# PaxInstrument-T400-at90usb.net
KiCad netlist of a schematic drawn in EAGLE
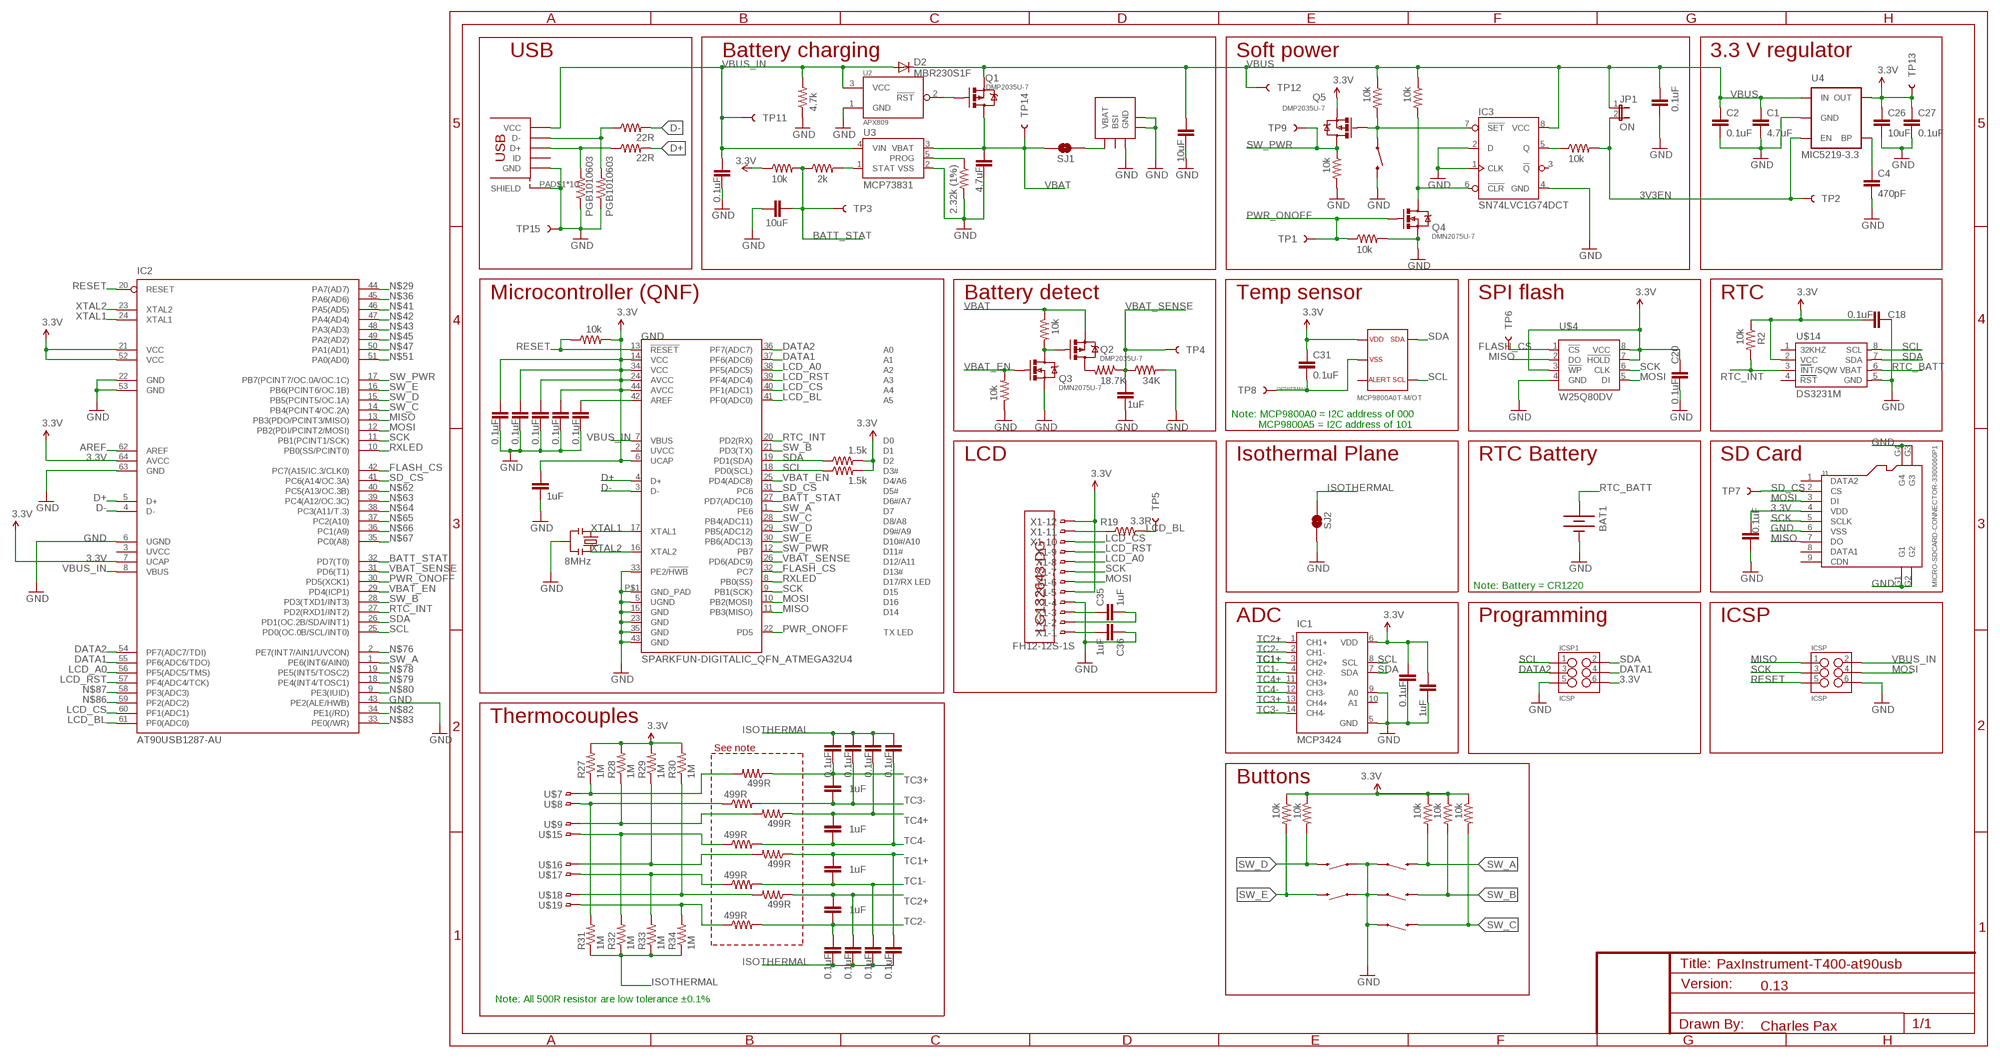
[diagram p0: schematic, sheet 1]

(export (version "E")
  (design (tool "Eeschema 10.0.6"))
  (components
    (comp (ref "BAT1")
      (value "BATTERY12MM")
      (footprint "eagle-import:BATTCON_12MM")
      (fields (field (name "MF") "Keystone Electronics") (field (name "MPN") "3000TR"))
      (libsource (lib "eagle-import") (part "BATTERY12MM"))
    )
    (comp (ref "C1")
      (value "4.7uF")
      (footprint "eagle-import:SPARKFUN-CAPACITORS_0603-CAP")
      (libsource (lib "eagle-import") (part "SPARKFUN-CAPACITORS_CAP0603-CAP"))
    )
    (comp (ref "C2")
      (value "0.1uF")
      (footprint "eagle-import:SPARKFUN-CAPACITORS_0603-CAP")
      (libsource (lib "eagle-import") (part "SPARKFUN-CAPACITORS_CAP0603-CAP"))
    )
    (comp (ref "C3")
      (value "0.1uF")
      (footprint "eagle-import:SPARKFUN-CAPACITORS_0603-CAP")
      (libsource (lib "eagle-import") (part "SPARKFUN-CAPACITORS_CAP0603-CAP"))
    )
    (comp (ref "C4")
      (value "470pF")
      (footprint "eagle-import:SPARKFUN-CAPACITORS_0603-CAP")
      (libsource (lib "eagle-import") (part "SPARKFUN-CAPACITORS_CAP0603-CAP"))
    )
    (comp (ref "C5")
      (value "0.1uF")
      (footprint "eagle-import:SPARKFUN-CAPACITORS_0603-CAP")
      (libsource (lib "eagle-import") (part "SPARKFUN-CAPACITORS_CAP0603-CAP"))
    )
    (comp (ref "C6")
      (value "0.1uF")
      (footprint "eagle-import:SPARKFUN-CAPACITORS_0603-CAP")
      (libsource (lib "eagle-import") (part "SPARKFUN-CAPACITORS_CAP0603-CAP"))
    )
    (comp (ref "C7")
      (value "1uF")
      (footprint "eagle-import:SPARKFUN-CAPACITORS_0603-CAP")
      (libsource (lib "eagle-import") (part "SPARKFUN-CAPACITORS_CAP0603-CAP"))
    )
    (comp (ref "C8")
      (value "1uF")
      (footprint "eagle-import:SPARKFUN-CAPACITORS_0603-CAP")
      (libsource (lib "eagle-import") (part "SPARKFUN-CAPACITORS_CAP0603-CAP"))
    )
    (comp (ref "C9")
      (value "4.7uF")
      (footprint "eagle-import:SPARKFUN-CAPACITORS_0603-CAP")
      (libsource (lib "eagle-import") (part "SPARKFUN-CAPACITORS_CAP0603-CAP"))
    )
    (comp (ref "C10")
      (value "1uF")
      (footprint "eagle-import:SPARKFUN-CAPACITORS_0603-CAP")
      (libsource (lib "eagle-import") (part "SPARKFUN-CAPACITORS_CAP0603-CAP"))
    )
    (comp (ref "C11")
      (value "1uF")
      (footprint "eagle-import:SPARKFUN-CAPACITORS_0603-CAP")
      (libsource (lib "eagle-import") (part "SPARKFUN-CAPACITORS_CAP0603-CAP"))
    )
    (comp (ref "C12")
      (value "10uF")
      (footprint "eagle-import:SPARKFUN-CAPACITORS_0603-CAP")
      (libsource (lib "eagle-import") (part "SPARKFUN-CAPACITORS_CAP0603-CAP"))
    )
    (comp (ref "C13")
      (value "0.1uF")
      (footprint "eagle-import:SPARKFUN-CAPACITORS_0603-CAP")
      (libsource (lib "eagle-import") (part "SPARKFUN-CAPACITORS_CAP0603-CAP"))
    )
    (comp (ref "C14")
      (value "0.1uF")
      (footprint "eagle-import:SPARKFUN-CAPACITORS_0603-CAP")
      (libsource (lib "eagle-import") (part "SPARKFUN-CAPACITORS_CAP0603-CAP"))
    )
    (comp (ref "C15")
      (value "0.1uF")
      (footprint "eagle-import:SPARKFUN-CAPACITORS_0603-CAP")
      (libsource (lib "eagle-import") (part "SPARKFUN-CAPACITORS_CAP0603-CAP"))
    )
    (comp (ref "C16")
      (value "0.1uF")
      (footprint "eagle-import:SPARKFUN-CAPACITORS_0603-CAP")
      (libsource (lib "eagle-import") (part "SPARKFUN-CAPACITORS_CAP0603-CAP"))
    )
    (comp (ref "C17")
      (value "0.1uF")
      (footprint "eagle-import:SPARKFUN-CAPACITORS_0603-CAP")
      (libsource (lib "eagle-import") (part "SPARKFUN-CAPACITORS_CAP0603-CAP"))
    )
    (comp (ref "C18")
      (value "0.1uF")
      (footprint "eagle-import:SPARKFUN-CAPACITORS_0603-CAP")
      (libsource (lib "eagle-import") (part "SPARKFUN-CAPACITORS_CAP0603-CAP"))
    )
    (comp (ref "C19")
      (value "1uF")
      (footprint "eagle-import:SPARKFUN-CAPACITORS_0603-CAP")
      (libsource (lib "eagle-import") (part "SPARKFUN-CAPACITORS_CAP0603-CAP"))
    )
    (comp (ref "C20")
      (value "0.1uF")
      (footprint "eagle-import:SPARKFUN-CAPACITORS_0603-CAP")
      (libsource (lib "eagle-import") (part "SPARKFUN-CAPACITORS_CAP0603-CAP"))
    )
    (comp (ref "C21")
      (value "0.1uF")
      (footprint "eagle-import:SPARKFUN-CAPACITORS_0603-CAP")
      (libsource (lib "eagle-import") (part "SPARKFUN-CAPACITORS_CAP0603-CAP"))
    )
    (comp (ref "C22")
      (value "10uF")
      (footprint "eagle-import:SPARKFUN-CAPACITORS_0603-CAP")
      (libsource (lib "eagle-import") (part "SPARKFUN-CAPACITORS_CAP0603-CAP"))
    )
    (comp (ref "C23")
      (value "1uF")
      (footprint "eagle-import:SPARKFUN-CAPACITORS_0603-CAP")
      (libsource (lib "eagle-import") (part "SPARKFUN-CAPACITORS_CAP0603-CAP"))
    )
    (comp (ref "C24")
      (value "0.1uF")
      (footprint "eagle-import:SPARKFUN-CAPACITORS_0603-CAP")
      (libsource (lib "eagle-import") (part "SPARKFUN-CAPACITORS_CAP0603-CAP"))
    )
    (comp (ref "C25")
      (value "0.1uF")
      (footprint "eagle-import:SPARKFUN-CAPACITORS_0603-CAP")
      (libsource (lib "eagle-import") (part "SPARKFUN-CAPACITORS_CAP0603-CAP"))
    )
    (comp (ref "C26")
      (value "10uF")
      (footprint "eagle-import:SPARKFUN-CAPACITORS_0603-CAP")
      (libsource (lib "eagle-import") (part "SPARKFUN-CAPACITORS_CAP0603-CAP"))
    )
    (comp (ref "C27")
      (value "0.1uF")
      (footprint "eagle-import:SPARKFUN-CAPACITORS_0603-CAP")
      (libsource (lib "eagle-import") (part "SPARKFUN-CAPACITORS_CAP0603-CAP"))
    )
    (comp (ref "C28")
      (value "0.1uF")
      (footprint "eagle-import:SPARKFUN-CAPACITORS_0603-CAP")
      (libsource (lib "eagle-import") (part "SPARKFUN-CAPACITORS_CAP0603-CAP"))
    )
    (comp (ref "C29")
      (value "0.1uF")
      (footprint "eagle-import:SPARKFUN-CAPACITORS_0603-CAP")
      (libsource (lib "eagle-import") (part "SPARKFUN-CAPACITORS_CAP0603-CAP"))
    )
    (comp (ref "C30")
      (value "1uF")
      (footprint "eagle-import:SPARKFUN-CAPACITORS_0603-CAP")
      (libsource (lib "eagle-import") (part "SPARKFUN-CAPACITORS_CAP0603-CAP"))
    )
    (comp (ref "C31")
      (value "0.1uF")
      (footprint "eagle-import:SPARKFUN-CAPACITORS_0603-CAP")
      (libsource (lib "eagle-import") (part "SPARKFUN-CAPACITORS_CAP0603-CAP"))
    )
    (comp (ref "C32")
      (value "0.1uF")
      (footprint "eagle-import:SPARKFUN-CAPACITORS_0603-CAP")
      (libsource (lib "eagle-import") (part "SPARKFUN-CAPACITORS_CAP0603-CAP"))
    )
    (comp (ref "C33")
      (value "0.1uF")
      (footprint "eagle-import:SPARKFUN-CAPACITORS_0603-CAP")
      (libsource (lib "eagle-import") (part "SPARKFUN-CAPACITORS_CAP0603-CAP"))
    )
    (comp (ref "C34")
      (value "0.1uF")
      (footprint "eagle-import:SPARKFUN-CAPACITORS_0603-CAP")
      (libsource (lib "eagle-import") (part "SPARKFUN-CAPACITORS_CAP0603-CAP"))
    )
    (comp (ref "C35")
      (value "1uF")
      (footprint "eagle-import:SPARKFUN-CAPACITORS_0603-CAP")
      (libsource (lib "eagle-import") (part "SPARKFUN-CAPACITORS_CAP0603-CAP"))
    )
    (comp (ref "C36")
      (value "1uF")
      (footprint "eagle-import:SPARKFUN-CAPACITORS_0603-CAP")
      (libsource (lib "eagle-import") (part "SPARKFUN-CAPACITORS_CAP0603-CAP"))
    )
    (comp (ref "C37")
      (value "0.1uF")
      (footprint "eagle-import:SPARKFUN-CAPACITORS_0603-CAP")
      (libsource (lib "eagle-import") (part "SPARKFUN-CAPACITORS_CAP0603-CAP"))
    )
    (comp (ref "D2")
      (value "MBR230S1F")
      (footprint "eagle-import:SOD123")
      (fields (field (name "MF") "DIODES INC") (field (name "MPN") "MBR230S1F-7"))
      (libsource (lib "eagle-import") (part "SPARKFUN-DISCRETESEMI_DIODESOD123SOD123"))
    )
    (comp (ref "GND")
      (value "SPARKFUN-DIGITALIC_QFN_ATMEGA32U4")
      (footprint "eagle-import:SPARKFUN-DIGITALIC_SPARKFUN-DIGITALIC_QFN-44")
      (fields (field (name "MF") "Atmel") (field (name "MPN") "ATMEGA32U4-MU"))
      (libsource (lib "eagle-import") (part "SPARKFUN-DIGITALIC_QFN_ATMEGA32U4"))
    )
    (comp (ref "IC1")
      (value "MCP3424")
      (footprint "eagle-import:SO14")
      (fields (field (name "MF") "Microchip Technology") (field (name "MPN") "MCP3424-E/SL"))
      (libsource (lib "eagle-import") (part "MCP3424"))
    )
    (comp (ref "IC2")
      (value "AT90USB1287-AU")
      (footprint "eagle-import:TQFP64")
      (libsource (lib "eagle-import") (part "AT90USB1287-AU"))
    )
    (comp (ref "IC3")
      (value "SN74LVC1G74DCT")
      (footprint "eagle-import:SSOP8")
      (fields (field (name "MF") "Texas Instruments") (field (name "MPN") "SN74LVC1G74DCTR "))
      (libsource (lib "eagle-import") (part "SN74LVC1G74DCT"))
    )
    (comp (ref "ICSP")
      (value "ICSP")
      (footprint "eagle-import:SPARKFUN-CONNECTORS_2X3_SMT_POSTS_PAXINSTRUMENT")
      (fields (field (name "MF") "FCI") (field (name "MPN") "95278-101A06LF"))
      (libsource (lib "eagle-import") (part "SPARKFUN-CONNECTORS_M03X2PAX"))
    )
    (comp (ref "ICSP1")
      (value "ICSP")
      (footprint "eagle-import:SPARKFUN-CONNECTORS_2X3_SMT_POSTS_PAXINSTRUMENT")
      (fields (field (name "MF") "FCI") (field (name "MPN") "95278-101A06LF"))
      (libsource (lib "eagle-import") (part "SPARKFUN-CONNECTORS_M03X2PAX"))
    )
    (comp (ref "J1")
      (value "MICRO-SDCARD-CONNECTOR-3300060P1")
      (footprint "eagle-import:9P-SMD-W-RING")
      (fields (field (name "MF") "SUNTECH") (field (name "MPN") "ST-TF-003A"))
      (libsource (lib "eagle-import") (part "MICRO-SDCARD-CONNECTOR-3300060P1"))
    )
    (comp (ref "JP1")
      (value "ON")
      (footprint "eagle-import:SJ_2S-NO")
      (libsource (lib "eagle-import") (part "JUMPER-2SMD-NO"))
    )
    (comp (ref "Q1")
      (value "DMP2035U-7")
      (footprint "eagle-import:SOT23")
      (fields (field (name "MF") "DIODES INC"))
      (libsource (lib "eagle-import") (part "MOSFET-PCHANNELSMT"))
    )
    (comp (ref "Q2")
      (value "DMP2035U-7")
      (footprint "eagle-import:SOT23")
      (fields (field (name "MF") "DIODES INC"))
      (libsource (lib "eagle-import") (part "MOSFET-PCHANNELSMT"))
    )
    (comp (ref "Q3")
      (value "DMN2075U-7")
      (footprint "eagle-import:SOT23")
      (fields (field (name "MF") "DIODES INC") (field (name "MPN") "DMN2075U-7 "))
      (libsource (lib "eagle-import") (part "MOSFET-NCHANNELSMT"))
    )
    (comp (ref "Q4")
      (value "DMN2075U-7")
      (footprint "eagle-import:SOT23")
      (fields (field (name "MF") "DIODES INC") (field (name "MPN") "DMN2075U-7 "))
      (libsource (lib "eagle-import") (part "MOSFET-NCHANNELSMT"))
    )
    (comp (ref "Q5")
      (value "DMP2035U-7")
      (footprint "eagle-import:SOT23")
      (fields (field (name "MF") "DIODES INC"))
      (libsource (lib "eagle-import") (part "MOSFET-PCHANNELSMT"))
    )
    (comp (ref "R1")
      (value "10k")
      (footprint "eagle-import:SPARKFUN-RESISTORS_0603-RES")
      (libsource (lib "eagle-import") (part "SPARKFUN-RESISTORS_RESISTOR0603-RES"))
    )
    (comp (ref "R2")
      (value "10k")
      (footprint "eagle-import:SPARKFUN-RESISTORS_0603-RES")
      (libsource (lib "eagle-import") (part "SPARKFUN-RESISTORS_RESISTOR0603-RES"))
    )
    (comp (ref "R3")
      (value "2.32k (1%)")
      (footprint "eagle-import:SPARKFUN-RESISTORS_0603-RES")
      (libsource (lib "eagle-import") (part "SPARKFUN-RESISTORS_RESISTOR0603-RES"))
    )
    (comp (ref "R4")
      (value "10k")
      (footprint "eagle-import:SPARKFUN-RESISTORS_0603-RES")
      (libsource (lib "eagle-import") (part "SPARKFUN-RESISTORS_RESISTOR0603-RES"))
    )
    (comp (ref "R5")
      (value "10k")
      (footprint "eagle-import:SPARKFUN-RESISTORS_0603-RES")
      (libsource (lib "eagle-import") (part "SPARKFUN-RESISTORS_RESISTOR0603-RES"))
    )
    (comp (ref "R6")
      (value "10k")
      (footprint "eagle-import:SPARKFUN-RESISTORS_0603-RES")
      (libsource (lib "eagle-import") (part "SPARKFUN-RESISTORS_RESISTOR0603-RES"))
    )
    (comp (ref "R7")
      (value "10k")
      (footprint "eagle-import:SPARKFUN-RESISTORS_0603-RES")
      (libsource (lib "eagle-import") (part "SPARKFUN-RESISTORS_RESISTOR0603-RES"))
    )
    (comp (ref "R8")
      (value "10k")
      (footprint "eagle-import:SPARKFUN-RESISTORS_0603-RES")
      (libsource (lib "eagle-import") (part "SPARKFUN-RESISTORS_RESISTOR0603-RES"))
    )
    (comp (ref "R9")
      (value "22R")
      (footprint "eagle-import:SPARKFUN-RESISTORS_0603-RES")
      (libsource (lib "eagle-import") (part "SPARKFUN-RESISTORS_RESISTOR0603-RES"))
    )
    (comp (ref "R10")
      (value "22R")
      (footprint "eagle-import:SPARKFUN-RESISTORS_0603-RES")
      (libsource (lib "eagle-import") (part "SPARKFUN-RESISTORS_RESISTOR0603-RES"))
    )
    (comp (ref "R11")
      (value "10k")
      (footprint "eagle-import:SPARKFUN-RESISTORS_0603-RES")
      (libsource (lib "eagle-import") (part "SPARKFUN-RESISTORS_RESISTOR0603-RES"))
    )
    (comp (ref "R12")
      (value "10k")
      (footprint "eagle-import:SPARKFUN-RESISTORS_0603-RES")
      (libsource (lib "eagle-import") (part "SPARKFUN-RESISTORS_RESISTOR0603-RES"))
    )
    (comp (ref "R13")
      (value "1.5k")
      (footprint "eagle-import:SPARKFUN-RESISTORS_0603-RES")
      (libsource (lib "eagle-import") (part "SPARKFUN-RESISTORS_RESISTOR0603-RES"))
    )
    (comp (ref "R14")
      (value "1.5k")
      (footprint "eagle-import:SPARKFUN-RESISTORS_0603-RES")
      (libsource (lib "eagle-import") (part "SPARKFUN-RESISTORS_RESISTOR0603-RES"))
    )
    (comp (ref "R15")
      (value "10k")
      (footprint "eagle-import:SPARKFUN-RESISTORS_0603-RES")
      (libsource (lib "eagle-import") (part "SPARKFUN-RESISTORS_RESISTOR0603-RES"))
    )
    (comp (ref "R16")
      (value "10k")
      (footprint "eagle-import:SPARKFUN-RESISTORS_0603-RES")
      (libsource (lib "eagle-import") (part "SPARKFUN-RESISTORS_RESISTOR0603-RES"))
    )
    (comp (ref "R17")
      (value "2k")
      (footprint "eagle-import:SPARKFUN-RESISTORS_0603-RES")
      (libsource (lib "eagle-import") (part "SPARKFUN-RESISTORS_RESISTOR0603-RES"))
    )
    (comp (ref "R18")
      (value "10k")
      (footprint "eagle-import:SPARKFUN-RESISTORS_0603-RES")
      (libsource (lib "eagle-import") (part "SPARKFUN-RESISTORS_RESISTOR0603-RES"))
    )
    (comp (ref "R19")
      (value "3.3R")
      (footprint "eagle-import:SPARKFUN-RESISTORS_0603-RES")
      (libsource (lib "eagle-import") (part "SPARKFUN-RESISTORS_RESISTOR0603-RES"))
    )
    (comp (ref "R20")
      (value "18.7K")
      (footprint "eagle-import:SPARKFUN-RESISTORS_0603-RES")
      (libsource (lib "eagle-import") (part "SPARKFUN-RESISTORS_RESISTOR0603-RES"))
    )
    (comp (ref "R21")
      (value "10k")
      (footprint "eagle-import:SPARKFUN-RESISTORS_0603-RES")
      (libsource (lib "eagle-import") (part "SPARKFUN-RESISTORS_RESISTOR0603-RES"))
    )
    (comp (ref "R22")
      (value "10k")
      (footprint "eagle-import:SPARKFUN-RESISTORS_0603-RES")
      (libsource (lib "eagle-import") (part "SPARKFUN-RESISTORS_RESISTOR0603-RES"))
    )
    (comp (ref "R23")
      (value "10k")
      (footprint "eagle-import:SPARKFUN-RESISTORS_0603-RES")
      (libsource (lib "eagle-import") (part "SPARKFUN-RESISTORS_RESISTOR0603-RES"))
    )
    (comp (ref "R24")
      (value "34K")
      (footprint "eagle-import:SPARKFUN-RESISTORS_0603-RES")
      (libsource (lib "eagle-import") (part "SPARKFUN-RESISTORS_RESISTOR0603-RES"))
    )
    (comp (ref "R25")
      (value "4.7k")
      (footprint "eagle-import:SPARKFUN-RESISTORS_0603-RES")
      (libsource (lib "eagle-import") (part "SPARKFUN-RESISTORS_RESISTOR0603-RES"))
    )
    (comp (ref "R27")
      (value "1M")
      (footprint "eagle-import:SPARKFUN-RESISTORS_0603-RES")
      (libsource (lib "eagle-import") (part "SPARKFUN-RESISTORS_RESISTOR0603-RES"))
    )
    (comp (ref "R28")
      (value "1M")
      (footprint "eagle-import:SPARKFUN-RESISTORS_0603-RES")
      (libsource (lib "eagle-import") (part "SPARKFUN-RESISTORS_RESISTOR0603-RES"))
    )
    (comp (ref "R29")
      (value "1M")
      (footprint "eagle-import:SPARKFUN-RESISTORS_0603-RES")
      (libsource (lib "eagle-import") (part "SPARKFUN-RESISTORS_RESISTOR0603-RES"))
    )
    (comp (ref "R30")
      (value "1M")
      (footprint "eagle-import:SPARKFUN-RESISTORS_0603-RES")
      (libsource (lib "eagle-import") (part "SPARKFUN-RESISTORS_RESISTOR0603-RES"))
    )
    (comp (ref "R31")
      (value "1M")
      (footprint "eagle-import:SPARKFUN-RESISTORS_0603-RES")
      (libsource (lib "eagle-import") (part "SPARKFUN-RESISTORS_RESISTOR0603-RES"))
    )
    (comp (ref "R32")
      (value "1M")
      (footprint "eagle-import:SPARKFUN-RESISTORS_0603-RES")
      (libsource (lib "eagle-import") (part "SPARKFUN-RESISTORS_RESISTOR0603-RES"))
    )
    (comp (ref "R33")
      (value "1M")
      (footprint "eagle-import:SPARKFUN-RESISTORS_0603-RES")
      (libsource (lib "eagle-import") (part "SPARKFUN-RESISTORS_RESISTOR0603-RES"))
    )
    (comp (ref "R34")
      (value "1M")
      (footprint "eagle-import:SPARKFUN-RESISTORS_0603-RES")
      (libsource (lib "eagle-import") (part "SPARKFUN-RESISTORS_RESISTOR0603-RES"))
    )
    (comp (ref "R35")
      (value "499R")
      (footprint "eagle-import:SPARKFUN-RESISTORS_0603-RES")
      (fields (field (name "MF") "Vishay") (field (name "MPN") "TNPW0603499RBEEA"))
      (libsource (lib "eagle-import") (part "SPARKFUN-RESISTORS_RESISTOR0603-RES"))
    )
    (comp (ref "R36")
      (value "499R")
      (footprint "eagle-import:SPARKFUN-RESISTORS_0603-RES")
      (fields (field (name "MF") "Vishay") (field (name "MPN") "TNPW0603499RBEEA"))
      (libsource (lib "eagle-import") (part "SPARKFUN-RESISTORS_RESISTOR0603-RES"))
    )
    (comp (ref "R37")
      (value "499R")
      (footprint "eagle-import:SPARKFUN-RESISTORS_0603-RES")
      (fields (field (name "MF") "Vishay") (field (name "MPN") "TNPW0603499RBEEA"))
      (libsource (lib "eagle-import") (part "SPARKFUN-RESISTORS_RESISTOR0603-RES"))
    )
    (comp (ref "R38")
      (value "499R")
      (footprint "eagle-import:SPARKFUN-RESISTORS_0603-RES")
      (fields (field (name "MF") "Vishay") (field (name "MPN") "TNPW0603499RBEEA"))
      (libsource (lib "eagle-import") (part "SPARKFUN-RESISTORS_RESISTOR0603-RES"))
    )
    (comp (ref "R39")
      (value "499R")
      (footprint "eagle-import:SPARKFUN-RESISTORS_0603-RES")
      (fields (field (name "MF") "Vishay") (field (name "MPN") "TNPW0603499RBEEA"))
      (libsource (lib "eagle-import") (part "SPARKFUN-RESISTORS_RESISTOR0603-RES"))
    )
    (comp (ref "R40")
      (value "499R")
      (footprint "eagle-import:SPARKFUN-RESISTORS_0603-RES")
      (fields (field (name "MF") "Vishay") (field (name "MPN") "TNPW0603499RBEEA"))
      (libsource (lib "eagle-import") (part "SPARKFUN-RESISTORS_RESISTOR0603-RES"))
    )
    (comp (ref "R41")
      (value "499R")
      (footprint "eagle-import:SPARKFUN-RESISTORS_0603-RES")
      (fields (field (name "MF") "Vishay") (field (name "MPN") "TNPW0603499RBEEA"))
      (libsource (lib "eagle-import") (part "SPARKFUN-RESISTORS_RESISTOR0603-RES"))
    )
    (comp (ref "R42")
      (value "499R")
      (footprint "eagle-import:SPARKFUN-RESISTORS_0603-RES")
      (fields (field (name "MF") "Vishay") (field (name "MPN") "TNPW0603499RBEEA"))
      (libsource (lib "eagle-import") (part "SPARKFUN-RESISTORS_RESISTOR0603-RES"))
    )
    (comp (ref "S1")
      (value "SWITCH-MOMENTARY-2SMD")
      (footprint "eagle-import:TACTILE_SWITCH_SMD")
      (fields (field (name "MF") "C&K Components") (field (name "MPN") "RS-187R05A2-DS MT RT"))
      (libsource (lib "eagle-import") (part "SWITCH-MOMENTARY-2SMD"))
    )
    (comp (ref "S2")
      (value "SWITCH-MOMENTARY-2SMD")
      (footprint "eagle-import:TACTILE_SWITCH_SMD")
      (fields (field (name "MF") "C&K Components") (field (name "MPN") "RS-187R05A2-DS MT RT"))
      (libsource (lib "eagle-import") (part "SWITCH-MOMENTARY-2SMD"))
    )
    (comp (ref "S3")
      (value "SWITCH-MOMENTARY-2SMD")
      (footprint "eagle-import:TACTILE_SWITCH_SMD")
      (fields (field (name "MF") "C&K Components") (field (name "MPN") "RS-187R05A2-DS MT RT"))
      (libsource (lib "eagle-import") (part "SWITCH-MOMENTARY-2SMD"))
    )
    (comp (ref "S4")
      (value "SWITCH-MOMENTARY-2SMD")
      (footprint "eagle-import:TACTILE_SWITCH_SMD")
      (fields (field (name "MF") "C&K Components") (field (name "MPN") "RS-187R05A2-DS MT RT"))
      (libsource (lib "eagle-import") (part "SWITCH-MOMENTARY-2SMD"))
    )
    (comp (ref "S5")
      (value "SWITCH-MOMENTARY-2SMD")
      (footprint "eagle-import:TACTILE_SWITCH_SMD")
      (fields (field (name "MF") "C&K Components") (field (name "MPN") "RS-187R05A2-DS MT RT"))
      (libsource (lib "eagle-import") (part "SWITCH-MOMENTARY-2SMD"))
    )
    (comp (ref "S6")
      (value "SWITCH-MOMENTARY-2SMD")
      (footprint "eagle-import:TACTILE_SWITCH_SMD")
      (fields (field (name "MF") "C&K Components") (field (name "MPN") "RS-187R05A2-DS MT RT"))
      (libsource (lib "eagle-import") (part "SWITCH-MOMENTARY-2SMD"))
    )
    (comp (ref "SJ1")
      (value "JUMPER-PAD-2-NC_BY_TRACE")
      (footprint "eagle-import:PAD-JUMPER-2-NC_BY_TRACE_YES_SILK")
      (libsource (lib "eagle-import") (part "JUMPER-PAD-2-NC_BY_TRACE"))
    )
    (comp (ref "SJ2")
      (value "JUMPER-PAD-2-NC_BY_TRACE")
      (footprint "eagle-import:PAD-JUMPER-2-NC_BY_TRACE_YES_SILK")
      (libsource (lib "eagle-import") (part "JUMPER-PAD-2-NC_BY_TRACE"))
    )
    (comp (ref "TP1")
      (value "PWR_ONOFF")
      (footprint "eagle-import:TP_15TH")
      (libsource (lib "eagle-import") (part "TEST-POINTTP_15TH_THRU"))
    )
    (comp (ref "TP2")
      (value "3V3_EN")
      (footprint "eagle-import:TP_15TH")
      (libsource (lib "eagle-import") (part "TEST-POINTTP_15TH_THRU"))
    )
    (comp (ref "TP3")
      (value "BATT_STAT")
      (footprint "eagle-import:TP_15TH")
      (libsource (lib "eagle-import") (part "TEST-POINTTP_15TH_THRU"))
    )
    (comp (ref "TP4")
      (value "VBAT_SENSE")
      (footprint "eagle-import:TP_15TH")
      (libsource (lib "eagle-import") (part "TEST-POINTTP_15TH_THRU"))
    )
    (comp (ref "TP5")
      (value "LCD_BL")
      (footprint "eagle-import:TP_15TH")
      (libsource (lib "eagle-import") (part "TEST-POINTTP_15TH_THRU"))
    )
    (comp (ref "TP6")
      (value "FLASH_CS")
      (footprint "eagle-import:TP_15TH")
      (libsource (lib "eagle-import") (part "TEST-POINTTP_15TH_THRU"))
    )
    (comp (ref "TP7")
      (value "SD_CS")
      (footprint "eagle-import:TP_15TH")
      (libsource (lib "eagle-import") (part "TEST-POINTTP_15TH_THRU"))
    )
    (comp (ref "TP8")
      (value "ISOTHERMAL")
      (footprint "eagle-import:TP_15TH")
      (libsource (lib "eagle-import") (part "TEST-POINTTP_15TH_THRU"))
    )
    (comp (ref "TP9")
      (value "SW_PWR")
      (footprint "eagle-import:TP_15TH")
      (libsource (lib "eagle-import") (part "TEST-POINTTP_15TH_THRU"))
    )
    (comp (ref "TP11")
      (value "VBUS_IN")
      (footprint "eagle-import:TP_15TH")
      (libsource (lib "eagle-import") (part "TEST-POINTTP_15TH_THRU"))
    )
    (comp (ref "TP12")
      (value "VBUS")
      (footprint "eagle-import:TP_15TH")
      (libsource (lib "eagle-import") (part "TEST-POINTTP_15TH_THRU"))
    )
    (comp (ref "TP13")
      (value "3.3V")
      (footprint "eagle-import:TP_15TH")
      (libsource (lib "eagle-import") (part "TEST-POINTTP_15TH_THRU"))
    )
    (comp (ref "TP14")
      (value "VBAT")
      (footprint "eagle-import:TP_15TH")
      (libsource (lib "eagle-import") (part "TEST-POINTTP_15TH_THRU"))
    )
    (comp (ref "TP15")
      (value "GND")
      (footprint "eagle-import:TP_15TH")
      (libsource (lib "eagle-import") (part "TEST-POINTTP_15TH_THRU"))
    )
    (comp (ref "U$1")
      (value "USB_MICROSMT+THRUHULE")
      (footprint "eagle-import:USB_MICRO_THRUHOLE")
      (fields (field (name "MF") "FCI") (field (name "MPN") "10118194-0001LF"))
      (libsource (lib "eagle-import") (part "USB_MICROSMT+THRUHULE"))
    )
    (comp (ref "U$2")
      (value "BL-5C-CONNECTOR")
      (footprint "eagle-import:BL-5C-CONNECTOR")
      (fields (field (name "MPN") "BC-4-3P (77H)"))
      (libsource (lib "eagle-import") (part "BL-5C-CONNECTOR"))
    )
    (comp (ref "U$4")
      (value "W25Q80DV")
      (footprint "eagle-import:CHARLESPAX_SOIC8M")
      (fields (field (name "MF") "Winbond Electronics") (field (name "MPN") "W25Q80DVSSIG-ND"))
      (libsource (lib "eagle-import") (part "W25Q80BV"))
    )
    (comp (ref "U$5")
      (value "LG132643-DG")
      (footprint "eagle-import:LG132643-DG")
      (fields (field (name "MPN") "LG132643-DW"))
      (libsource (lib "eagle-import") (part "LG132643-DG"))
    )
    (comp (ref "U$7")
      (value "TC-MINI-SINGLE")
      (footprint "eagle-import:TC-CLIP-SINGLE")
      (fields (field (name "MF") "Pax Instrument") (field (name "MPN") "Thermo-clip2"))
      (libsource (lib "eagle-import") (part "TC-MINI-SINGLE"))
    )
    (comp (ref "U$8")
      (value "TC-MINI-SINGLE")
      (footprint "eagle-import:TC-CLIP-SINGLE")
      (fields (field (name "MF") "Pax Instrument") (field (name "MPN") "Thermo-clip2"))
      (libsource (lib "eagle-import") (part "TC-MINI-SINGLE"))
    )
    (comp (ref "U$9")
      (value "TC-MINI-SINGLE")
      (footprint "eagle-import:TC-CLIP-SINGLE")
      (fields (field (name "MF") "Pax Instrument") (field (name "MPN") "Thermo-clip2"))
      (libsource (lib "eagle-import") (part "TC-MINI-SINGLE"))
    )
    (comp (ref "U$14")
      (value "DS3231M")
      (footprint "eagle-import:SOIC8")
      (fields (field (name "MF") "Maxim Integrated") (field (name "MPN") "DS3231MZ+"))
      (libsource (lib "eagle-import") (part "DS3231M"))
    )
    (comp (ref "U$15")
      (value "TC-MINI-SINGLE")
      (footprint "eagle-import:TC-CLIP-SINGLE")
      (fields (field (name "MF") "Pax Instrument") (field (name "MPN") "Thermo-clip2"))
      (libsource (lib "eagle-import") (part "TC-MINI-SINGLE"))
    )
    (comp (ref "U$16")
      (value "TC-MINI-SINGLE")
      (footprint "eagle-import:TC-CLIP-SINGLE")
      (fields (field (name "MF") "Pax Instrument") (field (name "MPN") "Thermo-clip2"))
      (libsource (lib "eagle-import") (part "TC-MINI-SINGLE"))
    )
    (comp (ref "U$17")
      (value "TC-MINI-SINGLE")
      (footprint "eagle-import:TC-CLIP-SINGLE")
      (fields (field (name "MF") "Pax Instrument") (field (name "MPN") "Thermo-clip2"))
      (libsource (lib "eagle-import") (part "TC-MINI-SINGLE"))
    )
    (comp (ref "U$18")
      (value "TC-MINI-SINGLE")
      (footprint "eagle-import:TC-CLIP-SINGLE")
      (fields (field (name "MF") "Pax Instrument") (field (name "MPN") "Thermo-clip2"))
      (libsource (lib "eagle-import") (part "TC-MINI-SINGLE"))
    )
    (comp (ref "U$19")
      (value "TC-MINI-SINGLE")
      (footprint "eagle-import:TC-CLIP-SINGLE")
      (fields (field (name "MF") "Pax Instrument") (field (name "MPN") "Thermo-clip2"))
      (libsource (lib "eagle-import") (part "TC-MINI-SINGLE"))
    )
    (comp (ref "U1")
      (value "MCP9800")
      (footprint "eagle-import:SOT23-5L")
      (fields (field (name "MF") "Microchip Technology") (field (name "MPN") "MCP9800A0T-M/OT"))
      (libsource (lib "eagle-import") (part "MCP9800"))
    )
    (comp (ref "U2")
      (value "APX809")
      (footprint "eagle-import:SOT23")
      (fields (field (name "MF") "DIODES INC") (field (name "MPN") "APX809-44SAG-7"))
      (libsource (lib "eagle-import") (part "APX809"))
    )
    (comp (ref "U3")
      (value "MCP73831")
      (footprint "eagle-import:SOT23-5")
      (fields (field (name "MF") "Microchip Technology") (field (name "MPN") "MCP73832T-2DCI/OT"))
      (libsource (lib "eagle-import") (part "MCP73831"))
    )
    (comp (ref "U4")
      (value "MIC5219-3.3V")
      (footprint "eagle-import:SOT23-5")
      (fields (field (name "MF") "Micrel") (field (name "MPN") "MIC5219-3.3YM5 TR"))
      (libsource (lib "eagle-import") (part "V_REG_LDOSMD"))
    )
    (comp (ref "X1")
      (value "FH12-12S-1S")
      (footprint "eagle-import:FH12-12S-1SH")
      (fields (field (name "MF") "Hirose Connector") (field (name "MPN") "FH12-12S-1SH(55)"))
      (libsource (lib "eagle-import") (part "FH12-12S-1S"))
    )
    (comp (ref "Y1")
      (value "RESONATORSMD")
      (footprint "eagle-import:RESONATOR-SMD")
      (fields (field (name "MF") "Murata Electronics") (field (name "MPN") "CSTCE8M00G52-R0"))
      (libsource (lib "eagle-import") (part "RESONATORSMD"))
    )
    (comp (ref "Z1")
      (value "PGB1010603")
      (footprint "eagle-import:SPARKFUN-RESISTORS_0603-RES")
      (fields (field (name "MF") "Littelfuse") (field (name "MPN") "PGB1010603NRHF"))
      (libsource (lib "eagle-import") (part "SPARKFUN-RESISTORS_RESISTOR0603-RES"))
    )
    (comp (ref "Z2")
      (value "PGB1010603")
      (footprint "eagle-import:SPARKFUN-RESISTORS_0603-RES")
      (fields (field (name "MF") "Littelfuse") (field (name "MPN") "PGB1010603NRHF"))
      (libsource (lib "eagle-import") (part "SPARKFUN-RESISTORS_RESISTOR0603-RES"))
    )
  )
  (nets
    (net (code "1") (name "/3V3EN") (class "Default")
      (node (ref "JP1") (pin "2") (pinfunction "2_2") (pintype "passive"))
      (node (ref "R21") (pin "2") (pinfunction "2_2") (pintype "passive"))
      (node (ref "TP2") (pin "P$1") (pinfunction "1_P$1") (pintype "bidirectional"))
      (node (ref "U4") (pin "3") (pinfunction "EN_3") (pintype "input"))
    )
    (net (code "2") (name "/AREF") (class "Default")
      (node (ref "C3") (pin "1") (pinfunction "1_1") (pintype "passive"))
      (node (ref "GND") (pin "42") (pinfunction "AREF_42") (pintype "bidirectional"))
      (node (ref "IC2") (pin "62") (pinfunction "AREF_62") (pintype "bidirectional"))
    )
    (net (code "3") (name "/BATT_STAT") (class "Default")
      (node (ref "C22") (pin "1") (pinfunction "1_1") (pintype "passive"))
      (node (ref "GND") (pin "27") (pinfunction "PD7(ADC10)_27") (pintype "bidirectional"))
      (node (ref "IC2") (pin "32") (pinfunction "PD7(T0)_32") (pintype "bidirectional"))
      (node (ref "R1") (pin "2") (pinfunction "2_2") (pintype "passive"))
      (node (ref "R17") (pin "1") (pinfunction "1_1") (pintype "passive"))
      (node (ref "TP3") (pin "P$1") (pinfunction "1_P$1") (pintype "bidirectional"))
    )
    (net (code "4") (name "/DATA1") (class "Default")
      (node (ref "GND") (pin "37") (pinfunction "PF6(ADC6)_37") (pintype "bidirectional"))
      (node (ref "IC2") (pin "55") (pinfunction "PF6(ADC6/TDO)_55") (pintype "bidirectional"))
      (node (ref "ICSP1") (pin "4") (pinfunction "4_4") (pintype "bidirectional"))
    )
    (net (code "5") (name "/DATA2") (class "Default")
      (node (ref "GND") (pin "36") (pinfunction "PF7(ADC7)_36") (pintype "bidirectional"))
      (node (ref "IC2") (pin "54") (pinfunction "PF7(ADC7/TDI)_54") (pintype "bidirectional"))
      (node (ref "ICSP1") (pin "3") (pinfunction "3_3") (pintype "bidirectional"))
    )
    (net (code "6") (name "/FLASH_CS") (class "Default")
      (node (ref "GND") (pin "32") (pinfunction "PC7_32") (pintype "bidirectional"))
      (node (ref "IC2") (pin "42") (pinfunction "PC7(A15/IC.3/CLK0)_42") (pintype "bidirectional"))
      (node (ref "TP6") (pin "P$1") (pinfunction "1_P$1") (pintype "bidirectional"))
      (node (ref "U$4") (pin "1") (pinfunction "~{CS}_1") (pintype "bidirectional"))
    )
    (net (code "7") (name "/ISOTHERMAL") (class "Default")
      (node (ref "C13") (pin "2") (pinfunction "2_2") (pintype "passive"))
      (node (ref "C14") (pin "2") (pinfunction "2_2") (pintype "passive"))
      (node (ref "C15") (pin "2") (pinfunction "2_2") (pintype "passive"))
      (node (ref "C16") (pin "2") (pinfunction "2_2") (pintype "passive"))
      (node (ref "C17") (pin "1") (pinfunction "1_1") (pintype "passive"))
      (node (ref "C24") (pin "1") (pinfunction "1_1") (pintype "passive"))
      (node (ref "C25") (pin "1") (pinfunction "1_1") (pintype "passive"))
      (node (ref "C31") (pin "2") (pinfunction "2_2") (pintype "passive"))
      (node (ref "C37") (pin "1") (pinfunction "1_1") (pintype "passive"))
      (node (ref "R31") (pin "1") (pinfunction "1_1") (pintype "passive"))
      (node (ref "R32") (pin "1") (pinfunction "1_1") (pintype "passive"))
      (node (ref "R33") (pin "1") (pinfunction "1_1") (pintype "passive"))
      (node (ref "R34") (pin "1") (pinfunction "1_1") (pintype "passive"))
      (node (ref "SJ2") (pin "2") (pinfunction "2_2") (pintype "passive"))
      (node (ref "TP8") (pin "P$1") (pinfunction "1_P$1") (pintype "bidirectional"))
      (node (ref "U1") (pin "2") (pinfunction "2_2") (pintype "bidirectional"))
    )
    (net (code "8") (name "/LCD_A0") (class "Default")
      (node (ref "GND") (pin "38") (pinfunction "PF5(ADC5)_38") (pintype "bidirectional"))
      (node (ref "IC2") (pin "56") (pinfunction "PF5(ADC5/TMS)_56") (pintype "bidirectional"))
      (node (ref "X1") (pin "8") (pinfunction "1_8") (pintype "passive"))
    )
    (net (code "9") (name "/LCD_BL") (class "Default")
      (node (ref "GND") (pin "41") (pinfunction "PF0(ADC0)_41") (pintype "bidirectional"))
      (node (ref "IC2") (pin "61") (pinfunction "PF0(ADC0)_61") (pintype "bidirectional"))
      (node (ref "R19") (pin "2") (pinfunction "2_2") (pintype "passive"))
      (node (ref "TP5") (pin "P$1") (pinfunction "1_P$1") (pintype "bidirectional"))
    )
    (net (code "10") (name "/LCD_CS") (class "Default")
      (node (ref "GND") (pin "40") (pinfunction "PF1(ADC1)_40") (pintype "bidirectional"))
      (node (ref "IC2") (pin "60") (pinfunction "PF1(ADC1)_60") (pintype "bidirectional"))
      (node (ref "X1") (pin "10") (pinfunction "1_10") (pintype "passive"))
    )
    (net (code "11") (name "/LCD_RST") (class "Default")
      (node (ref "GND") (pin "39") (pinfunction "PF4(ADC4)_39") (pintype "bidirectional"))
      (node (ref "IC2") (pin "57") (pinfunction "PF4(ADC4/TCK)_57") (pintype "bidirectional"))
      (node (ref "X1") (pin "9") (pinfunction "1_9") (pintype "passive"))
    )
    (net (code "12") (name "/MISO") (class "Default")
      (node (ref "GND") (pin "11") (pinfunction "PB3(MISO)_11") (pintype "bidirectional"))
      (node (ref "IC2") (pin "13") (pinfunction "PB3(PDO/PCINT3/MISO)_13") (pintype "bidirectional"))
      (node (ref "ICSP") (pin "1") (pinfunction "1_1") (pintype "bidirectional"))
      (node (ref "J1") (pin "7") (pinfunction "DO_7") (pintype "bidirectional"))
      (node (ref "U$4") (pin "2") (pinfunction "DO_2") (pintype "bidirectional"))
    )
    (net (code "13") (name "/MOSI") (class "Default")
      (node (ref "GND") (pin "10") (pinfunction "PB2(MOSI)_10") (pintype "bidirectional"))
      (node (ref "IC2") (pin "12") (pinfunction "PB2(PDI/PCINT2/MOSI)_12") (pintype "bidirectional"))
      (node (ref "ICSP") (pin "4") (pinfunction "4_4") (pintype "bidirectional"))
      (node (ref "J1") (pin "3") (pinfunction "DI_3") (pintype "bidirectional"))
      (node (ref "U$4") (pin "5") (pinfunction "DI_5") (pintype "bidirectional"))
      (node (ref "X1") (pin "6") (pinfunction "1_6") (pintype "passive"))
    )
    (net (code "14") (name "/N$29") (class "Default")
      (node (ref "IC2") (pin "44") (pinfunction "PA7(AD7)_44") (pintype "bidirectional"))
    )
    (net (code "15") (name "/N$36") (class "Default")
      (node (ref "IC2") (pin "45") (pinfunction "PA6(AD6)_45") (pintype "bidirectional"))
    )
    (net (code "16") (name "/N$41") (class "Default")
      (node (ref "IC2") (pin "46") (pinfunction "PA5(AD5)_46") (pintype "bidirectional"))
    )
    (net (code "17") (name "/N$42") (class "Default")
      (node (ref "IC2") (pin "47") (pinfunction "PA4(AD4)_47") (pintype "bidirectional"))
    )
    (net (code "18") (name "/N$43") (class "Default")
      (node (ref "IC2") (pin "48") (pinfunction "PA3(AD3)_48") (pintype "bidirectional"))
    )
    (net (code "19") (name "/N$45") (class "Default")
      (node (ref "IC2") (pin "49") (pinfunction "PA2(AD2)_49") (pintype "bidirectional"))
    )
    (net (code "20") (name "/N$47") (class "Default")
      (node (ref "IC2") (pin "50") (pinfunction "PA1(AD1)_50") (pintype "bidirectional"))
    )
    (net (code "21") (name "/N$51") (class "Default")
      (node (ref "IC2") (pin "51") (pinfunction "PA0(AD0)_51") (pintype "bidirectional"))
    )
    (net (code "22") (name "/N$62") (class "Default")
      (node (ref "IC2") (pin "40") (pinfunction "PC5(A13/OC.3B)_40") (pintype "bidirectional"))
    )
    (net (code "23") (name "/N$63") (class "Default")
      (node (ref "IC2") (pin "39") (pinfunction "PC4(A12/OC.3C)_39") (pintype "bidirectional"))
    )
    (net (code "24") (name "/N$64") (class "Default")
      (node (ref "IC2") (pin "38") (pinfunction "PC3(A11/T.3)_38") (pintype "bidirectional"))
    )
    (net (code "25") (name "/N$65") (class "Default")
      (node (ref "IC2") (pin "37") (pinfunction "PC2(A10)_37") (pintype "bidirectional"))
    )
    (net (code "26") (name "/N$66") (class "Default")
      (node (ref "IC2") (pin "36") (pinfunction "PC1(A9)_36") (pintype "bidirectional"))
    )
    (net (code "27") (name "/N$67") (class "Default")
      (node (ref "IC2") (pin "35") (pinfunction "PC0(A8)_35") (pintype "bidirectional"))
    )
    (net (code "28") (name "/N$76") (class "Default")
      (node (ref "IC2") (pin "2") (pinfunction "PE7(INT7/AIN1/UVCON)_2") (pintype "bidirectional"))
    )
    (net (code "29") (name "/N$78") (class "Default")
      (node (ref "IC2") (pin "19") (pinfunction "PE5(INT5/TOSC2)_19") (pintype "bidirectional"))
    )
    (net (code "30") (name "/N$79") (class "Default")
      (node (ref "IC2") (pin "18") (pinfunction "PE4(INT4/TOSC1)_18") (pintype "bidirectional"))
    )
    (net (code "31") (name "/N$80") (class "Default")
      (node (ref "IC2") (pin "9") (pinfunction "PE3(IUID)_9") (pintype "bidirectional"))
    )
    (net (code "32") (name "/N$82") (class "Default")
      (node (ref "IC2") (pin "34") (pinfunction "PE1(/RD)_34") (pintype "bidirectional"))
    )
    (net (code "33") (name "/N$83") (class "Default")
      (node (ref "IC2") (pin "33") (pinfunction "PE0(/WR)_33") (pintype "bidirectional"))
    )
    (net (code "34") (name "/N$86") (class "Default")
      (node (ref "IC2") (pin "59") (pinfunction "PF2(ADC2)_59") (pintype "bidirectional"))
    )
    (net (code "35") (name "/N$87") (class "Default")
      (node (ref "IC2") (pin "58") (pinfunction "PF3(ADC3)_58") (pintype "bidirectional"))
    )
    (net (code "36") (name "/PWR_ONOFF") (class "Default")
      (node (ref "GND") (pin "22") (pinfunction "PD5_22") (pintype "bidirectional"))
      (node (ref "IC2") (pin "30") (pinfunction "PD5(XCK1)_30") (pintype "bidirectional"))
      (node (ref "Q4") (pin "1") (pinfunction "G_1") (pintype "passive"))
      (node (ref "R22") (pin "1") (pinfunction "1_1") (pintype "passive"))
      (node (ref "TP1") (pin "P$1") (pinfunction "1_P$1") (pintype "bidirectional"))
    )
    (net (code "37") (name "/RESET") (class "Default")
      (node (ref "GND") (pin "13") (pinfunction "~{RESET}_13") (pintype "bidirectional"))
      (node (ref "IC2") (pin "20") (pinfunction "RESET_20") (pintype "input"))
      (node (ref "ICSP") (pin "5") (pinfunction "5_5") (pintype "bidirectional"))
      (node (ref "R4") (pin "1") (pinfunction "1_1") (pintype "passive"))
    )
    (net (code "38") (name "/RTC_BATT") (class "Default")
      (node (ref "BAT1") (pin "PWR@1") (pinfunction "+_PWR@1") (pintype "power_in"))
      (node (ref "U$14") (pin "6") (pinfunction "VBAT_6") (pintype "input"))
    )
    (net (code "39") (name "/RTC_INT") (class "Default")
      (node (ref "GND") (pin "20") (pinfunction "PD2(RX)_20") (pintype "bidirectional"))
      (node (ref "IC2") (pin "27") (pinfunction "PD2(RXD1/INT2)_27") (pintype "bidirectional"))
      (node (ref "R2") (pin "2") (pinfunction "2_2") (pintype "passive"))
      (node (ref "U$14") (pin "3") (pinfunction "INT/SQW_3") (pintype "output"))
    )
    (net (code "40") (name "/RXLED") (class "Default")
      (node (ref "GND") (pin "8") (pinfunction "PB0(SS)_8") (pintype "bidirectional"))
      (node (ref "IC2") (pin "10") (pinfunction "PB0(SS/PCINT0)_10") (pintype "bidirectional"))
    )
    (net (code "41") (name "/SCK") (class "Default")
      (node (ref "GND") (pin "9") (pinfunction "PB1(SCK)_9") (pintype "bidirectional"))
      (node (ref "IC2") (pin "11") (pinfunction "PB1(PCINT1/SCK)_11") (pintype "bidirectional"))
      (node (ref "ICSP") (pin "3") (pinfunction "3_3") (pintype "bidirectional"))
      (node (ref "J1") (pin "5") (pinfunction "SCLK_5") (pintype "bidirectional"))
      (node (ref "U$4") (pin "6") (pinfunction "CLK_6") (pintype "bidirectional"))
      (node (ref "X1") (pin "7") (pinfunction "1_7") (pintype "passive"))
    )
    (net (code "42") (name "/SCL") (class "Default")
      (node (ref "GND") (pin "18") (pinfunction "PD0(SCL)_18") (pintype "bidirectional"))
      (node (ref "IC1") (pin "8") (pinfunction "SCL_8") (pintype "input"))
      (node (ref "IC2") (pin "25") (pinfunction "PD0(OC.0B/SCL/INT0)_25") (pintype "bidirectional"))
      (node (ref "ICSP1") (pin "1") (pinfunction "1_1") (pintype "bidirectional"))
      (node (ref "R14") (pin "1") (pinfunction "1_1") (pintype "passive"))
      (node (ref "U$14") (pin "8") (pinfunction "SCL_8") (pintype "input"))
      (node (ref "U1") (pin "4") (pinfunction "4_4") (pintype "bidirectional"))
    )
    (net (code "43") (name "/SDA") (class "Default")
      (node (ref "GND") (pin "19") (pinfunction "PD1(SDA)_19") (pintype "bidirectional"))
      (node (ref "IC1") (pin "7") (pinfunction "SDA_7") (pintype "bidirectional"))
      (node (ref "IC2") (pin "26") (pinfunction "PD1(OC.2B/SDA/INT1)_26") (pintype "bidirectional"))
      (node (ref "ICSP1") (pin "2") (pinfunction "2_2") (pintype "bidirectional"))
      (node (ref "R13") (pin "1") (pinfunction "1_1") (pintype "passive"))
      (node (ref "U$14") (pin "7") (pinfunction "SDA_7") (pintype "bidirectional"))
      (node (ref "U1") (pin "5") (pinfunction "5_5") (pintype "bidirectional"))
    )
    (net (code "44") (name "/SD_CS") (class "Default")
      (node (ref "GND") (pin "31") (pinfunction "PC6_31") (pintype "bidirectional"))
      (node (ref "IC2") (pin "41") (pinfunction "PC6(A14/OC.3A)_41") (pintype "bidirectional"))
      (node (ref "J1") (pin "2") (pinfunction "CS_2") (pintype "bidirectional"))
      (node (ref "TP7") (pin "P$1") (pinfunction "1_P$1") (pintype "bidirectional"))
    )
    (net (code "45") (name "/SW_PWR") (class "Default")
      (node (ref "GND") (pin "12") (pinfunction "PB7_12") (pintype "bidirectional"))
      (node (ref "IC2") (pin "17") (pinfunction "PB7(PCINT7/OC.0A/OC.1C)_17") (pintype "bidirectional"))
      (node (ref "Q5") (pin "3") (pinfunction "D_3") (pintype "passive"))
      (node (ref "R18") (pin "1") (pinfunction "1_1") (pintype "passive"))
      (node (ref "TP9") (pin "P$1") (pinfunction "1_P$1") (pintype "bidirectional"))
    )
    (net (code "46") (name "/TC1+") (class "Default")
      (node (ref "C10") (pin "1") (pinfunction "1_1") (pintype "passive"))
      (node (ref "C16") (pin "1") (pinfunction "1_1") (pintype "passive"))
      (node (ref "IC1") (pin "3") (pinfunction "CH2+_3") (pintype "input"))
      (node (ref "R39") (pin "1") (pinfunction "1_1") (pintype "passive"))
    )
    (net (code "47") (name "/TC1-") (class "Default")
      (node (ref "C10") (pin "2") (pinfunction "2_2") (pintype "passive"))
      (node (ref "C15") (pin "1") (pinfunction "1_1") (pintype "passive"))
      (node (ref "IC1") (pin "4") (pinfunction "CH2-_4") (pintype "input"))
      (node (ref "R41") (pin "2") (pinfunction "2_2") (pintype "passive"))
    )
    (net (code "48") (name "/TC2+") (class "Default")
      (node (ref "C11") (pin "1") (pinfunction "1_1") (pintype "passive"))
      (node (ref "C14") (pin "1") (pinfunction "1_1") (pintype "passive"))
      (node (ref "IC1") (pin "1") (pinfunction "CH1+_1") (pintype "input"))
      (node (ref "R40") (pin "1") (pinfunction "1_1") (pintype "passive"))
    )
    (net (code "49") (name "/TC2-") (class "Default")
      (node (ref "C11") (pin "2") (pinfunction "2_2") (pintype "passive"))
      (node (ref "C13") (pin "1") (pinfunction "1_1") (pintype "passive"))
      (node (ref "IC1") (pin "2") (pinfunction "CH1-_2") (pintype "input"))
      (node (ref "R42") (pin "2") (pinfunction "2_2") (pintype "passive"))
    )
    (net (code "50") (name "/TC3+") (class "Default")
      (node (ref "C17") (pin "2") (pinfunction "2_2") (pintype "passive"))
      (node (ref "C7") (pin "1") (pinfunction "1_1") (pintype "passive"))
      (node (ref "IC1") (pin "13") (pinfunction "CH4+_13") (pintype "input"))
      (node (ref "R35") (pin "1") (pinfunction "1_1") (pintype "passive"))
    )
    (net (code "51") (name "/TC3-") (class "Default")
      (node (ref "C24") (pin "2") (pinfunction "2_2") (pintype "passive"))
      (node (ref "C7") (pin "2") (pinfunction "2_2") (pintype "passive"))
      (node (ref "IC1") (pin "14") (pinfunction "CH4-_14") (pintype "input"))
      (node (ref "R36") (pin "2") (pinfunction "2_2") (pintype "passive"))
    )
    (net (code "52") (name "/TC4+") (class "Default")
      (node (ref "C25") (pin "2") (pinfunction "2_2") (pintype "passive"))
      (node (ref "C8") (pin "1") (pinfunction "1_1") (pintype "passive"))
      (node (ref "IC1") (pin "11") (pinfunction "CH3+_11") (pintype "input"))
      (node (ref "R37") (pin "1") (pinfunction "1_1") (pintype "passive"))
    )
    (net (code "53") (name "/TC4-") (class "Default")
      (node (ref "C37") (pin "2") (pinfunction "2_2") (pintype "passive"))
      (node (ref "C8") (pin "2") (pinfunction "2_2") (pintype "passive"))
      (node (ref "IC1") (pin "12") (pinfunction "CH3-_12") (pintype "input"))
      (node (ref "R38") (pin "2") (pinfunction "2_2") (pintype "passive"))
    )
    (net (code "54") (name "/UVCC") (class "Default")
      (node (ref "IC2") (pin "3") (pinfunction "UVCC_3") (pintype "power_in"))
    )
    (net (code "55") (name "/VBAT") (class "Default")
      (node (ref "C9") (pin "1") (pinfunction "1_1") (pintype "passive"))
      (node (ref "Q1") (pin "3") (pinfunction "D_3") (pintype "passive"))
      (node (ref "Q2") (pin "2") (pinfunction "S_2") (pintype "passive"))
      (node (ref "R5") (pin "1") (pinfunction "1_1") (pintype "passive"))
      (node (ref "SJ1") (pin "1") (pinfunction "1_1") (pintype "passive"))
      (node (ref "TP14") (pin "P$1") (pinfunction "1_P$1") (pintype "bidirectional"))
      (node (ref "U3") (pin "3") (pinfunction "VBAT_3") (pintype "power_in"))
    )
    (net (code "56") (name "/VBAT_EN") (class "Default")
      (node (ref "GND") (pin "25") (pinfunction "PD4(ADC8)_25") (pintype "bidirectional"))
      (node (ref "IC2") (pin "29") (pinfunction "PD4(ICP1)_29") (pintype "bidirectional"))
      (node (ref "Q3") (pin "1") (pinfunction "G_1") (pintype "passive"))
      (node (ref "R23") (pin "2") (pinfunction "2_2") (pintype "passive"))
    )
    (net (code "57") (name "/VBAT_SENSE") (class "Default")
      (node (ref "C23") (pin "1") (pinfunction "1_1") (pintype "passive"))
      (node (ref "GND") (pin "26") (pinfunction "PD6(ADC9)_26") (pintype "bidirectional"))
      (node (ref "IC2") (pin "31") (pinfunction "PD6(T1)_31") (pintype "bidirectional"))
      (node (ref "R20") (pin "1") (pinfunction "1_1") (pintype "passive"))
      (node (ref "R24") (pin "1") (pinfunction "1_1") (pintype "passive"))
      (node (ref "TP4") (pin "P$1") (pinfunction "1_P$1") (pintype "bidirectional"))
    )
    (net (code "58") (name "/VBUS") (class "Default")
      (node (ref "C1") (pin "1") (pinfunction "1_1") (pintype "passive"))
      (node (ref "C12") (pin "1") (pinfunction "1_1") (pintype "passive"))
      (node (ref "C2") (pin "1") (pinfunction "1_1") (pintype "passive"))
      (node (ref "C28") (pin "1") (pinfunction "1_1") (pintype "passive"))
      (node (ref "D2") (pin "C") (pinfunction "C_C") (pintype "passive"))
      (node (ref "IC3") (pin "8") (pinfunction "VCC_8") (pintype "power_in"))
      (node (ref "JP1") (pin "1") (pinfunction "1_1") (pintype "passive"))
      (node (ref "Q1") (pin "2") (pinfunction "S_2") (pintype "passive"))
      (node (ref "R6") (pin "1") (pinfunction "1_1") (pintype "passive"))
      (node (ref "R7") (pin "1") (pinfunction "1_1") (pintype "passive"))
      (node (ref "TP12") (pin "P$1") (pinfunction "1_P$1") (pintype "bidirectional"))
      (node (ref "U4") (pin "1") (pinfunction "IN_1") (pintype "input"))
    )
    (net (code "59") (name "/VBUS_IN") (class "Default")
      (node (ref "C6") (pin "1") (pinfunction "1_1") (pintype "passive"))
      (node (ref "D2") (pin "A") (pinfunction "A_A") (pintype "passive"))
      (node (ref "GND") (pin "7") (pinfunction "VBUS_7") (pintype "bidirectional"))
      (node (ref "IC2") (pin "8") (pinfunction "VBUS_8") (pintype "power_in"))
      (node (ref "ICSP") (pin "2") (pinfunction "2_2") (pintype "bidirectional"))
      (node (ref "R25") (pin "2") (pinfunction "2_2") (pintype "passive"))
      (node (ref "TP11") (pin "P$1") (pinfunction "1_P$1") (pintype "bidirectional"))
      (node (ref "U$1") (pin "PIN$1") (pinfunction "VCC_PIN$1") (pintype "bidirectional"))
      (node (ref "U2") (pin "3") (pinfunction "VCC_3") (pintype "power_in"))
      (node (ref "U3") (pin "4") (pinfunction "VIN_4") (pintype "power_in"))
    )
    (net (code "60") (name "/XTAL1") (class "Default")
      (node (ref "GND") (pin "17") (pinfunction "XTAL1_17") (pintype "bidirectional"))
      (node (ref "IC2") (pin "24") (pinfunction "XTAL1_24") (pintype "bidirectional"))
      (node (ref "Y1") (pin "1") (pinfunction "1_1") (pintype "passive"))
    )
    (net (code "61") (name "/XTAL2") (class "Default")
      (node (ref "GND") (pin "16") (pinfunction "XTAL2_16") (pintype "bidirectional"))
      (node (ref "IC2") (pin "23") (pinfunction "XTAL2_23") (pintype "bidirectional"))
      (node (ref "Y1") (pin "3") (pinfunction "3_3") (pintype "passive"))
    )
    (net (code "62") (name "3.3V") (class "Default")
      (node (ref "C18") (pin "1") (pinfunction "1_1") (pintype "passive"))
      (node (ref "C19") (pin "1") (pinfunction "1_1") (pintype "passive"))
      (node (ref "C20") (pin "2") (pinfunction "2_2") (pintype "passive"))
      (node (ref "C21") (pin "2") (pinfunction "2_2") (pintype "passive"))
      (node (ref "C26") (pin "1") (pinfunction "1_1") (pintype "passive"))
      (node (ref "C27") (pin "1") (pinfunction "1_1") (pintype "passive"))
      (node (ref "C29") (pin "1") (pinfunction "1_1") (pintype "passive"))
      (node (ref "C30") (pin "1") (pinfunction "1_1") (pintype "passive"))
      (node (ref "C31") (pin "1") (pinfunction "1_1") (pintype "passive"))
      (node (ref "C32") (pin "1") (pinfunction "1_1") (pintype "passive"))
      (node (ref "C33") (pin "1") (pinfunction "1_1") (pintype "passive"))
      (node (ref "C34") (pin "1") (pinfunction "1_1") (pintype "passive"))
      (node (ref "C5") (pin "1") (pinfunction "1_1") (pintype "passive"))
      (node (ref "GND") (pin "14") (pinfunction "VCC_14") (pintype "bidirectional"))
      (node (ref "GND") (pin "24") (pinfunction "AVCC_24") (pintype "bidirectional"))
      (node (ref "GND") (pin "34") (pinfunction "VCC_34") (pintype "bidirectional"))
      (node (ref "GND") (pin "44") (pinfunction "AVCC_44") (pintype "bidirectional"))
      (node (ref "GND") (pin "6") (pinfunction "UCAP_6") (pintype "bidirectional"))
      (node (ref "IC1") (pin "6") (pinfunction "VDD_6") (pintype "power_in"))
      (node (ref "IC2") (pin "21") (pinfunction "VCC_21") (pintype "power_in"))
      (node (ref "IC2") (pin "52") (pinfunction "VCC_52") (pintype "power_in"))
      (node (ref "IC2") (pin "64") (pinfunction "AVCC_64") (pintype "bidirectional"))
      (node (ref "IC2") (pin "7") (pinfunction "UCAP_7") (pintype "power_in"))
      (node (ref "ICSP1") (pin "6") (pinfunction "6_6") (pintype "bidirectional"))
      (node (ref "J1") (pin "4") (pinfunction "VDD_4") (pintype "bidirectional"))
      (node (ref "Q5") (pin "2") (pinfunction "S_2") (pintype "passive"))
      (node (ref "R1") (pin "1") (pinfunction "1_1") (pintype "passive"))
      (node (ref "R11") (pin "1") (pinfunction "1_1") (pintype "passive"))
      (node (ref "R12") (pin "1") (pinfunction "1_1") (pintype "passive"))
      (node (ref "R13") (pin "2") (pinfunction "2_2") (pintype "passive"))
      (node (ref "R14") (pin "2") (pinfunction "2_2") (pintype "passive"))
      (node (ref "R15") (pin "1") (pinfunction "1_1") (pintype "passive"))
      (node (ref "R16") (pin "1") (pinfunction "1_1") (pintype "passive"))
      (node (ref "R2") (pin "1") (pinfunction "1_1") (pintype "passive"))
      (node (ref "R27") (pin "2") (pinfunction "2_2") (pintype "passive"))
      (node (ref "R28") (pin "2") (pinfunction "2_2") (pintype "passive"))
      (node (ref "R29") (pin "2") (pinfunction "2_2") (pintype "passive"))
      (node (ref "R30") (pin "2") (pinfunction "2_2") (pintype "passive"))
      (node (ref "R4") (pin "2") (pinfunction "2_2") (pintype "passive"))
      (node (ref "R8") (pin "1") (pinfunction "1_1") (pintype "passive"))
      (node (ref "TP13") (pin "P$1") (pinfunction "1_P$1") (pintype "bidirectional"))
      (node (ref "U$14") (pin "2") (pinfunction "VCC_2") (pintype "power_in"))
      (node (ref "U$4") (pin "3") (pinfunction "~{WP}_3") (pintype "bidirectional"))
      (node (ref "U$4") (pin "7") (pinfunction "~{HOLD}_7") (pintype "bidirectional"))
      (node (ref "U$4") (pin "8") (pinfunction "VCC_8") (pintype "bidirectional"))
      (node (ref "U1") (pin "1") (pinfunction "1_1") (pintype "bidirectional"))
      (node (ref "U4") (pin "5") (pinfunction "OUT_5") (pintype "passive"))
      (node (ref "X1") (pin "12") (pinfunction "1_12") (pintype "passive"))
      (node (ref "X1") (pin "5") (pinfunction "1_5") (pintype "passive"))
    )
    (net (code "63") (name "D+") (class "Default")
      (node (ref "GND") (pin "4") (pinfunction "D+_4") (pintype "bidirectional"))
      (node (ref "IC2") (pin "5") (pinfunction "D+_5") (pintype "bidirectional"))
      (node (ref "R9") (pin "2") (pinfunction "2_2") (pintype "passive"))
    )
    (net (code "64") (name "D-") (class "Default")
      (node (ref "GND") (pin "3") (pinfunction "D-_3") (pintype "bidirectional"))
      (node (ref "IC2") (pin "4") (pinfunction "D-_4") (pintype "bidirectional"))
      (node (ref "R10") (pin "2") (pinfunction "2_2") (pintype "passive"))
    )
    (net (code "65") (name "GND") (class "Default")
      (node (ref "BAT1") (pin "GND") (pinfunction "-_GND") (pintype "power_in"))
      (node (ref "C1") (pin "2") (pinfunction "2_2") (pintype "passive"))
      (node (ref "C12") (pin "2") (pinfunction "2_2") (pintype "passive"))
      (node (ref "C18") (pin "2") (pinfunction "2_2") (pintype "passive"))
      (node (ref "C19") (pin "2") (pinfunction "2_2") (pintype "passive"))
      (node (ref "C2") (pin "2") (pinfunction "2_2") (pintype "passive"))
      (node (ref "C20") (pin "1") (pinfunction "1_1") (pintype "passive"))
      (node (ref "C21") (pin "1") (pinfunction "1_1") (pintype "passive"))
      (node (ref "C22") (pin "2") (pinfunction "2_2") (pintype "passive"))
      (node (ref "C23") (pin "2") (pinfunction "2_2") (pintype "passive"))
      (node (ref "C26") (pin "2") (pinfunction "2_2") (pintype "passive"))
      (node (ref "C27") (pin "2") (pinfunction "2_2") (pintype "passive"))
      (node (ref "C28") (pin "2") (pinfunction "2_2") (pintype "passive"))
      (node (ref "C29") (pin "2") (pinfunction "2_2") (pintype "passive"))
      (node (ref "C3") (pin "2") (pinfunction "2_2") (pintype "passive"))
      (node (ref "C30") (pin "2") (pinfunction "2_2") (pintype "passive"))
      (node (ref "C32") (pin "2") (pinfunction "2_2") (pintype "passive"))
      (node (ref "C33") (pin "2") (pinfunction "2_2") (pintype "passive"))
      (node (ref "C34") (pin "2") (pinfunction "2_2") (pintype "passive"))
      (node (ref "C36") (pin "1") (pinfunction "1_1") (pintype "passive"))
      (node (ref "C4") (pin "2") (pinfunction "2_2") (pintype "passive"))
      (node (ref "C5") (pin "2") (pinfunction "2_2") (pintype "passive"))
      (node (ref "C6") (pin "2") (pinfunction "2_2") (pintype "passive"))
      (node (ref "C9") (pin "2") (pinfunction "2_2") (pintype "passive"))
      (node (ref "GND") (pin "15") (pinfunction "GND_15") (pintype "bidirectional"))
      (node (ref "GND") (pin "23") (pinfunction "GND_23") (pintype "bidirectional"))
      (node (ref "GND") (pin "33") (pinfunction "PE2/~{HWB}_33") (pintype "bidirectional"))
      (node (ref "GND") (pin "35") (pinfunction "GND_35") (pintype "bidirectional"))
      (node (ref "GND") (pin "43") (pinfunction "GND_43") (pintype "bidirectional"))
      (node (ref "GND") (pin "5") (pinfunction "UGND_5") (pintype "bidirectional"))
      (node (ref "GND") (pin "P$1") (pinfunction "GND_PAD_P$1") (pintype "bidirectional"))
      (node (ref "IC1") (pin "5") (pinfunction "GND_5") (pintype "power_in"))
      (node (ref "IC1") (pin "9") (pinfunction "A0_9") (pintype "input"))
      (node (ref "IC2") (pin "22") (pinfunction "GND_22") (pintype "power_in"))
      (node (ref "IC2") (pin "43") (pinfunction "PE2(ALE/HWB)_43") (pintype "bidirectional"))
      (node (ref "IC2") (pin "53") (pinfunction "GND_53") (pintype "power_in"))
      (node (ref "IC2") (pin "6") (pinfunction "UGND_6") (pintype "power_in"))
      (node (ref "IC2") (pin "63") (pinfunction "GND_63") (pintype "power_in"))
      (node (ref "IC3") (pin "1") (pinfunction "CLK_1") (pintype "input"))
      (node (ref "IC3") (pin "2") (pinfunction "D_2") (pintype "input"))
      (node (ref "IC3") (pin "4") (pinfunction "GND_4") (pintype "power_in"))
      (node (ref "ICSP") (pin "6") (pinfunction "6_6") (pintype "bidirectional"))
      (node (ref "ICSP1") (pin "5") (pinfunction "5_5") (pintype "bidirectional"))
      (node (ref "J1") (pin "6") (pinfunction "VSS_6") (pintype "bidirectional"))
      (node (ref "J1") (pin "G1") (pinfunction "G1_G1") (pintype "bidirectional"))
      (node (ref "J1") (pin "G2") (pinfunction "G2_G2") (pintype "bidirectional"))
      (node (ref "J1") (pin "G3") (pinfunction "G3_G3") (pintype "bidirectional"))
      (node (ref "J1") (pin "G4") (pinfunction "G4_G4") (pintype "bidirectional"))
      (node (ref "Q3") (pin "2") (pinfunction "S_2") (pintype "passive"))
      (node (ref "Q4") (pin "2") (pinfunction "S_2") (pintype "passive"))
      (node (ref "R18") (pin "2") (pinfunction "2_2") (pintype "passive"))
      (node (ref "R22") (pin "2") (pinfunction "2_2") (pintype "passive"))
      (node (ref "R23") (pin "1") (pinfunction "1_1") (pintype "passive"))
      (node (ref "R24") (pin "2") (pinfunction "2_2") (pintype "passive"))
      (node (ref "R25") (pin "1") (pinfunction "1_1") (pintype "passive"))
      (node (ref "R3") (pin "2") (pinfunction "2_2") (pintype "passive"))
      (node (ref "S1") (pin "1") (pinfunction "1_1") (pintype "passive"))
      (node (ref "S2") (pin "1") (pinfunction "1_1") (pintype "passive"))
      (node (ref "S3") (pin "1") (pinfunction "1_1") (pintype "passive"))
      (node (ref "S4") (pin "1") (pinfunction "1_1") (pintype "passive"))
      (node (ref "S5") (pin "1") (pinfunction "1_1") (pintype "passive"))
      (node (ref "S6") (pin "3") (pinfunction "2_3") (pintype "passive"))
      (node (ref "SJ2") (pin "1") (pinfunction "1_1") (pintype "passive"))
      (node (ref "TP15") (pin "P$1") (pinfunction "1_P$1") (pintype "bidirectional"))
      (node (ref "U$1") (pin "PAD$1") (pinfunction "SHIELD_PAD$1") (pintype "bidirectional"))
      (node (ref "U$1") (pin "PAD$10") (pinfunction "SHIELD_PAD$10") (pintype "bidirectional"))
      (node (ref "U$1") (pin "PAD$2") (pinfunction "SHIELD_PAD$2") (pintype "bidirectional"))
      (node (ref "U$1") (pin "PAD$3") (pinfunction "SHIELD_PAD$3") (pintype "bidirectional"))
      (node (ref "U$1") (pin "PAD$4") (pinfunction "SHIELD_PAD$4") (pintype "bidirectional"))
      (node (ref "U$1") (pin "PAD$5") (pinfunction "SHIELD_PAD$5") (pintype "bidirectional"))
      (node (ref "U$1") (pin "PAD$6") (pinfunction "SHIELD_PAD$6") (pintype "bidirectional"))
      (node (ref "U$1") (pin "PAD$7") (pinfunction "SHIELD_PAD$7") (pintype "bidirectional"))
      (node (ref "U$1") (pin "PAD$8") (pinfunction "SHIELD_PAD$8") (pintype "bidirectional"))
      (node (ref "U$1") (pin "PAD$9") (pinfunction "SHIELD_PAD$9") (pintype "bidirectional"))
      (node (ref "U$1") (pin "PIN$5") (pinfunction "GND_PIN$5") (pintype "bidirectional"))
      (node (ref "U$14") (pin "5") (pinfunction "GND_5") (pintype "power_in"))
      (node (ref "U$2") (pin "P$3") (pinfunction "GND_P$3") (pintype "bidirectional"))
      (node (ref "U$2") (pin "P$4") (pinfunction "P$4_P$4") (pintype "bidirectional"))
      (node (ref "U$2") (pin "P$5") (pinfunction "P$5_P$5") (pintype "bidirectional"))
      (node (ref "U$4") (pin "4") (pinfunction "GND_4") (pintype "bidirectional"))
      (node (ref "U2") (pin "1") (pinfunction "GND_1") (pintype "power_in"))
      (node (ref "U3") (pin "2") (pinfunction "VSS_2") (pintype "power_in"))
      (node (ref "U4") (pin "2") (pinfunction "GND_2") (pintype "input"))
      (node (ref "X1") (pin "4") (pinfunction "1_4") (pintype "passive"))
      (node (ref "Y1") (pin "2") (pinfunction "2_2") (pintype "passive"))
      (node (ref "Z1") (pin "1") (pinfunction "1_1") (pintype "passive"))
      (node (ref "Z2") (pin "1") (pinfunction "1_1") (pintype "passive"))
    )
    (net (code "66") (name "Net-(C36-Pad2)") (class "Default")
      (node (ref "C36") (pin "2") (pinfunction "2_2") (pintype "passive"))
      (node (ref "X1") (pin "1") (pinfunction "1_1") (pintype "passive"))
    )
    (net (code "67") (name "Net-(IC3-Q)") (class "Default")
      (node (ref "IC3") (pin "5") (pinfunction "Q_5") (pintype "output"))
      (node (ref "R21") (pin "1") (pinfunction "1_1") (pintype "passive"))
    )
    (net (code "68") (name "Net-(IC3-~{CLR})") (class "Default")
      (node (ref "IC3") (pin "6") (pinfunction "~{CLR}_6") (pintype "input"))
      (node (ref "Q4") (pin "3") (pinfunction "D_3") (pintype "passive"))
      (node (ref "R7") (pin "2") (pinfunction "2_2") (pintype "passive"))
    )
    (net (code "69") (name "Net-(IC3-~{SET})") (class "Default")
      (node (ref "IC3") (pin "7") (pinfunction "~{SET}_7") (pintype "input"))
      (node (ref "Q5") (pin "1") (pinfunction "G_1") (pintype "passive"))
      (node (ref "R6") (pin "2") (pinfunction "2_2") (pintype "passive"))
      (node (ref "S6") (pin "1") (pinfunction "1_1") (pintype "passive"))
    )
    (net (code "70") (name "Net-(Q1-G)") (class "Default")
      (node (ref "Q1") (pin "1") (pinfunction "G_1") (pintype "passive"))
      (node (ref "U2") (pin "2") (pinfunction "~{RST}_2") (pintype "bidirectional"))
    )
    (net (code "71") (name "Net-(Q2-D)") (class "Default")
      (node (ref "Q2") (pin "3") (pinfunction "D_3") (pintype "passive"))
      (node (ref "R20") (pin "2") (pinfunction "2_2") (pintype "passive"))
    )
    (net (code "72") (name "Net-(Q2-G)") (class "Default")
      (node (ref "Q2") (pin "1") (pinfunction "G_1") (pintype "passive"))
      (node (ref "Q3") (pin "3") (pinfunction "D_3") (pintype "passive"))
      (node (ref "R5") (pin "2") (pinfunction "2_2") (pintype "passive"))
    )
    (net (code "73") (name "Net-(U$1-D+)") (class "Default")
      (node (ref "R9") (pin "1") (pinfunction "1_1") (pintype "passive"))
      (node (ref "U$1") (pin "PIN$3") (pinfunction "D+_PIN$3") (pintype "bidirectional"))
      (node (ref "Z1") (pin "2") (pinfunction "2_2") (pintype "passive"))
    )
    (net (code "74") (name "Net-(U$1-D-)") (class "Default")
      (node (ref "R10") (pin "1") (pinfunction "1_1") (pintype "passive"))
      (node (ref "U$1") (pin "PIN$2") (pinfunction "D-_PIN$2") (pintype "bidirectional"))
      (node (ref "Z2") (pin "2") (pinfunction "2_2") (pintype "passive"))
    )
    (net (code "75") (name "Net-(U$2-VBAT)") (class "Default")
      (node (ref "SJ1") (pin "2") (pinfunction "2_2") (pintype "passive"))
      (node (ref "U$2") (pin "P$1") (pinfunction "VBAT_P$1") (pintype "bidirectional"))
    )
    (net (code "76") (name "Net-(U$7-1)") (class "Default")
      (node (ref "R27") (pin "1") (pinfunction "1_1") (pintype "passive"))
      (node (ref "R35") (pin "2") (pinfunction "2_2") (pintype "passive"))
      (node (ref "U$7") (pin "P$1") (pinfunction "1_P$1") (pintype "passive"))
    )
    (net (code "77") (name "Net-(U$8-1)") (class "Default")
      (node (ref "R31") (pin "2") (pinfunction "2_2") (pintype "passive"))
      (node (ref "R36") (pin "1") (pinfunction "1_1") (pintype "passive"))
      (node (ref "U$8") (pin "P$1") (pinfunction "1_P$1") (pintype "passive"))
    )
    (net (code "78") (name "Net-(U$9-1)") (class "Default")
      (node (ref "R28") (pin "1") (pinfunction "1_1") (pintype "passive"))
      (node (ref "R37") (pin "2") (pinfunction "2_2") (pintype "passive"))
      (node (ref "U$9") (pin "P$1") (pinfunction "1_P$1") (pintype "passive"))
    )
    (net (code "79") (name "Net-(U$15-1)") (class "Default")
      (node (ref "R32") (pin "2") (pinfunction "2_2") (pintype "passive"))
      (node (ref "R38") (pin "1") (pinfunction "1_1") (pintype "passive"))
      (node (ref "U$15") (pin "P$1") (pinfunction "1_P$1") (pintype "passive"))
    )
    (net (code "80") (name "Net-(U$16-1)") (class "Default")
      (node (ref "R29") (pin "1") (pinfunction "1_1") (pintype "passive"))
      (node (ref "R39") (pin "2") (pinfunction "2_2") (pintype "passive"))
      (node (ref "U$16") (pin "P$1") (pinfunction "1_P$1") (pintype "passive"))
    )
    (net (code "81") (name "Net-(U$17-1)") (class "Default")
      (node (ref "R33") (pin "2") (pinfunction "2_2") (pintype "passive"))
      (node (ref "R41") (pin "1") (pinfunction "1_1") (pintype "passive"))
      (node (ref "U$17") (pin "P$1") (pinfunction "1_P$1") (pintype "passive"))
    )
    (net (code "82") (name "Net-(U$18-1)") (class "Default")
      (node (ref "R30") (pin "1") (pinfunction "1_1") (pintype "passive"))
      (node (ref "R40") (pin "2") (pinfunction "2_2") (pintype "passive"))
      (node (ref "U$18") (pin "P$1") (pinfunction "1_P$1") (pintype "passive"))
    )
    (net (code "83") (name "Net-(U$19-1)") (class "Default")
      (node (ref "R34") (pin "2") (pinfunction "2_2") (pintype "passive"))
      (node (ref "R42") (pin "1") (pinfunction "1_1") (pintype "passive"))
      (node (ref "U$19") (pin "P$1") (pinfunction "1_P$1") (pintype "passive"))
    )
    (net (code "84") (name "Net-(U3-PROG)") (class "Default")
      (node (ref "R3") (pin "1") (pinfunction "1_1") (pintype "passive"))
      (node (ref "U3") (pin "5") (pinfunction "PROG_5") (pintype "input"))
    )
    (net (code "85") (name "Net-(U3-STAT)") (class "Default")
      (node (ref "R17") (pin "2") (pinfunction "2_2") (pintype "passive"))
      (node (ref "U3") (pin "1") (pinfunction "STAT_1") (pintype "output"))
    )
    (net (code "86") (name "Net-(U4-BP)") (class "Default")
      (node (ref "C4") (pin "1") (pinfunction "1_1") (pintype "passive"))
      (node (ref "U4") (pin "4") (pinfunction "BP_4") (pintype "input"))
    )
    (net (code "87") (name "Net-(X1C-1)") (class "Default")
      (node (ref "R19") (pin "1") (pinfunction "1_1") (pintype "passive"))
      (node (ref "X1") (pin "11") (pinfunction "1_11") (pintype "passive"))
    )
    (net (code "88") (name "Net-(X1E-1)") (class "Default")
      (node (ref "C35") (pin "2") (pinfunction "2_2") (pintype "passive"))
      (node (ref "X1") (pin "2") (pinfunction "1_2") (pintype "passive"))
    )
    (net (code "89") (name "Net-(X1F-1)") (class "Default")
      (node (ref "C35") (pin "1") (pinfunction "1_1") (pintype "passive"))
      (node (ref "X1") (pin "3") (pinfunction "1_3") (pintype "passive"))
    )
    (net (code "90") (name "SW_A") (class "Default")
      (node (ref "GND") (pin "1") (pinfunction "PE6_1") (pintype "bidirectional"))
      (node (ref "IC2") (pin "1") (pinfunction "PE6(INT6/AIN0)_1") (pintype "bidirectional"))
      (node (ref "R8") (pin "2") (pinfunction "2_2") (pintype "passive"))
      (node (ref "S3") (pin "3") (pinfunction "2_3") (pintype "passive"))
    )
    (net (code "91") (name "SW_B") (class "Default")
      (node (ref "GND") (pin "21") (pinfunction "PD3(TX)_21") (pintype "bidirectional"))
      (node (ref "IC2") (pin "28") (pinfunction "PD3(TXD1/INT3)_28") (pintype "bidirectional"))
      (node (ref "R11") (pin "2") (pinfunction "2_2") (pintype "passive"))
      (node (ref "S2") (pin "3") (pinfunction "2_3") (pintype "passive"))
    )
    (net (code "92") (name "SW_C") (class "Default")
      (node (ref "GND") (pin "28") (pinfunction "PB4(ADC11)_28") (pintype "bidirectional"))
      (node (ref "IC2") (pin "14") (pinfunction "PB4(PCINT4/OC.2A)_14") (pintype "bidirectional"))
      (node (ref "R12") (pin "2") (pinfunction "2_2") (pintype "passive"))
      (node (ref "S1") (pin "3") (pinfunction "2_3") (pintype "passive"))
    )
    (net (code "93") (name "SW_D") (class "Default")
      (node (ref "GND") (pin "29") (pinfunction "PB5(ADC12)_29") (pintype "bidirectional"))
      (node (ref "IC2") (pin "15") (pinfunction "PB5(PCINT5/OC.1A)_15") (pintype "bidirectional"))
      (node (ref "R15") (pin "2") (pinfunction "2_2") (pintype "passive"))
      (node (ref "S4") (pin "3") (pinfunction "2_3") (pintype "passive"))
    )
    (net (code "94") (name "SW_E") (class "Default")
      (node (ref "GND") (pin "30") (pinfunction "PB6(ADC13)_30") (pintype "bidirectional"))
      (node (ref "IC2") (pin "16") (pinfunction "PB6(PCINT6/OC.1B)_16") (pintype "bidirectional"))
      (node (ref "R16") (pin "2") (pinfunction "2_2") (pintype "passive"))
      (node (ref "S5") (pin "3") (pinfunction "2_3") (pintype "passive"))
    )
    (net (code "95") (name "unconnected-(GND-UVCC-Pad2)") (class "Default")
      (node (ref "GND") (pin "2") (pinfunction "UVCC_2") (pintype "bidirectional"))
    )
    (net (code "96") (name "unconnected-(IC1-A1-Pad10)") (class "Default")
      (node (ref "IC1") (pin "10") (pinfunction "A1_10") (pintype "input"))
    )
    (net (code "97") (name "unconnected-(IC3-~{Q}-Pad3)") (class "Default")
      (node (ref "IC3") (pin "3") (pinfunction "~{Q}_3") (pintype "output"))
    )
    (net (code "98") (name "unconnected-(J1-CDN-Pad9)") (class "Default")
      (node (ref "J1") (pin "9") (pinfunction "CDN_9") (pintype "bidirectional"))
    )
    (net (code "99") (name "unconnected-(J1-DATA1-Pad8)") (class "Default")
      (node (ref "J1") (pin "8") (pinfunction "DATA1_8") (pintype "bidirectional"))
    )
    (net (code "100") (name "unconnected-(J1-DATA2-Pad1)") (class "Default")
      (node (ref "J1") (pin "1") (pinfunction "DATA2_1") (pintype "bidirectional"))
    )
    (net (code "101") (name "unconnected-(U$1-ID-PadPIN$4)") (class "Default")
      (node (ref "U$1") (pin "PIN$4") (pinfunction "ID_PIN$4") (pintype "bidirectional"))
    )
    (net (code "102") (name "unconnected-(U$2-BSI-PadP$2)") (class "Default")
      (node (ref "U$2") (pin "P$2") (pinfunction "BSI_P$2") (pintype "bidirectional"))
    )
    (net (code "103") (name "unconnected-(U$14-32KHZ-Pad1)") (class "Default")
      (node (ref "U$14") (pin "1") (pinfunction "32KHZ_1") (pintype "output"))
    )
    (net (code "104") (name "unconnected-(U$14-RST-Pad4)") (class "Default")
      (node (ref "U$14") (pin "4") (pinfunction "RST_4") (pintype "bidirectional"))
    )
    (net (code "105") (name "unconnected-(U1-Pad3)") (class "Default")
      (node (ref "U1") (pin "3") (pinfunction "3_3") (pintype "bidirectional"))
    )
  )
)
